# phono_preamp.net
KiCad netlist of a schematic drawn in EAGLE
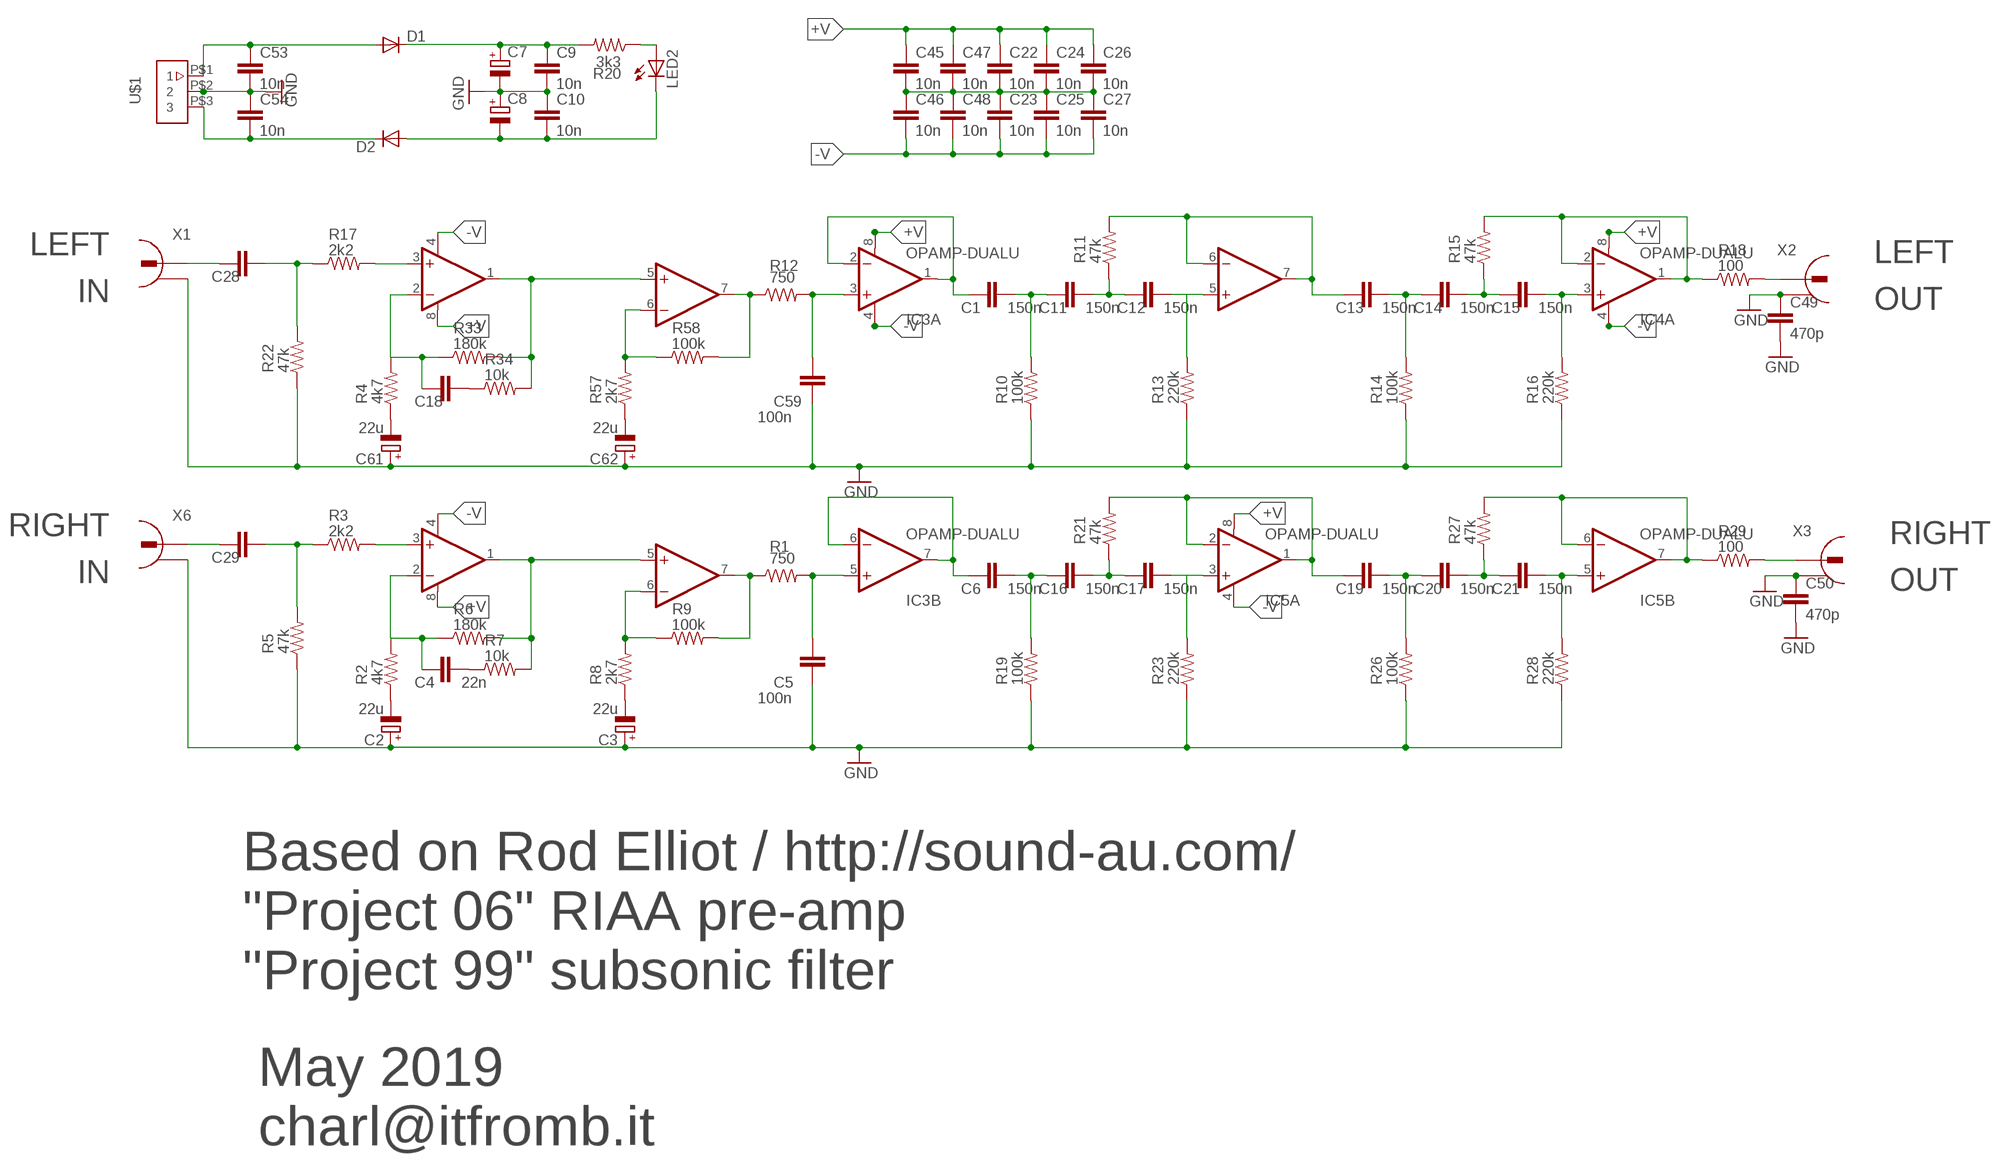
[diagram p0: schematic, sheet 1]

(export (version "E")
  (design (tool "Eeschema 10.0.6"))
  (components
    (comp (ref "C1")
      (value "150n")
      (footprint "eagle-import:C1206")
      (libsource (lib "eagle-import") (part "C-EUC1206"))
    )
    (comp (ref "C2")
      (value "22u")
      (footprint "eagle-import:PANASONIC_C")
      (libsource (lib "eagle-import") (part "CPOL-EUC"))
    )
    (comp (ref "C3")
      (value "22u")
      (footprint "eagle-import:PANASONIC_C")
      (libsource (lib "eagle-import") (part "CPOL-EUC"))
    )
    (comp (ref "C4")
      (value "22n")
      (footprint "eagle-import:C1206")
      (libsource (lib "eagle-import") (part "C-EUC1206"))
    )
    (comp (ref "C5")
      (value "100n")
      (footprint "eagle-import:C1206")
      (libsource (lib "eagle-import") (part "C-EUC1206"))
    )
    (comp (ref "C6")
      (value "150n")
      (footprint "eagle-import:C1206")
      (libsource (lib "eagle-import") (part "C-EUC1206"))
    )
    (comp (ref "C7")
      (value "CPOL-EUSANYO_SMD_F12")
      (footprint "eagle-import:SANYO-OSCON_SMD_F12")
      (libsource (lib "eagle-import") (part "stereo_5.1_mixer_CPOL-EUSANYO_SMD_F12"))
    )
    (comp (ref "C8")
      (value "CPOL-EUSANYO_SMD_F12")
      (footprint "eagle-import:SANYO-OSCON_SMD_F12")
      (libsource (lib "eagle-import") (part "stereo_5.1_mixer_CPOL-EUSANYO_SMD_F12"))
    )
    (comp (ref "C9")
      (value "10n")
      (footprint "eagle-import:C1206")
      (libsource (lib "eagle-import") (part "C-EUC1206"))
    )
    (comp (ref "C10")
      (value "10n")
      (footprint "eagle-import:C1206")
      (libsource (lib "eagle-import") (part "C-EUC1206"))
    )
    (comp (ref "C11")
      (value "150n")
      (footprint "eagle-import:C1206")
      (libsource (lib "eagle-import") (part "C-EUC1206"))
    )
    (comp (ref "C12")
      (value "150n")
      (footprint "eagle-import:C1206")
      (libsource (lib "eagle-import") (part "C-EUC1206"))
    )
    (comp (ref "C13")
      (value "150n")
      (footprint "eagle-import:C1206")
      (libsource (lib "eagle-import") (part "C-EUC1206"))
    )
    (comp (ref "C14")
      (value "150n")
      (footprint "eagle-import:C1206")
      (libsource (lib "eagle-import") (part "C-EUC1206"))
    )
    (comp (ref "C15")
      (value "150n")
      (footprint "eagle-import:C1206")
      (libsource (lib "eagle-import") (part "C-EUC1206"))
    )
    (comp (ref "C16")
      (value "150n")
      (footprint "eagle-import:C1206")
      (libsource (lib "eagle-import") (part "C-EUC1206"))
    )
    (comp (ref "C17")
      (value "150n")
      (footprint "eagle-import:C1206")
      (libsource (lib "eagle-import") (part "C-EUC1206"))
    )
    (comp (ref "C18")
      (value "22n")
      (footprint "eagle-import:C1206")
      (libsource (lib "eagle-import") (part "C-EUC1206"))
    )
    (comp (ref "C19")
      (value "150n")
      (footprint "eagle-import:C1206")
      (libsource (lib "eagle-import") (part "C-EUC1206"))
    )
    (comp (ref "C20")
      (value "150n")
      (footprint "eagle-import:C1206")
      (libsource (lib "eagle-import") (part "C-EUC1206"))
    )
    (comp (ref "C21")
      (value "150n")
      (footprint "eagle-import:C1206")
      (libsource (lib "eagle-import") (part "C-EUC1206"))
    )
    (comp (ref "C22")
      (value "10n")
      (footprint "eagle-import:C1206")
      (libsource (lib "eagle-import") (part "C-EUC1206"))
    )
    (comp (ref "C23")
      (value "10n")
      (footprint "eagle-import:C1206")
      (libsource (lib "eagle-import") (part "C-EUC1206"))
    )
    (comp (ref "C24")
      (value "10n")
      (footprint "eagle-import:C1206")
      (libsource (lib "eagle-import") (part "C-EUC1206"))
    )
    (comp (ref "C25")
      (value "10n")
      (footprint "eagle-import:C1206")
      (libsource (lib "eagle-import") (part "C-EUC1206"))
    )
    (comp (ref "C26")
      (value "10n")
      (footprint "eagle-import:C1206")
      (libsource (lib "eagle-import") (part "C-EUC1206"))
    )
    (comp (ref "C27")
      (value "10n")
      (footprint "eagle-import:C1206")
      (libsource (lib "eagle-import") (part "C-EUC1206"))
    )
    (comp (ref "C28")
      (value "C-EUC1206")
      (footprint "eagle-import:C1206")
      (libsource (lib "eagle-import") (part "C-EUC1206"))
    )
    (comp (ref "C29")
      (value "C-EUC1206")
      (footprint "eagle-import:C1206")
      (libsource (lib "eagle-import") (part "C-EUC1206"))
    )
    (comp (ref "C45")
      (value "10n")
      (footprint "eagle-import:C1206")
      (libsource (lib "eagle-import") (part "C-EUC1206"))
    )
    (comp (ref "C46")
      (value "10n")
      (footprint "eagle-import:C1206")
      (libsource (lib "eagle-import") (part "C-EUC1206"))
    )
    (comp (ref "C47")
      (value "10n")
      (footprint "eagle-import:C1206")
      (libsource (lib "eagle-import") (part "C-EUC1206"))
    )
    (comp (ref "C48")
      (value "10n")
      (footprint "eagle-import:C1206")
      (libsource (lib "eagle-import") (part "C-EUC1206"))
    )
    (comp (ref "C49")
      (value "470p")
      (footprint "eagle-import:C1206")
      (libsource (lib "eagle-import") (part "C-EUC1206"))
    )
    (comp (ref "C50")
      (value "470p")
      (footprint "eagle-import:C1206")
      (libsource (lib "eagle-import") (part "C-EUC1206"))
    )
    (comp (ref "C53")
      (value "10n")
      (footprint "eagle-import:C1206")
      (libsource (lib "eagle-import") (part "C-EUC1206"))
    )
    (comp (ref "C54")
      (value "10n")
      (footprint "eagle-import:C1206")
      (libsource (lib "eagle-import") (part "C-EUC1206"))
    )
    (comp (ref "C59")
      (value "100n")
      (footprint "eagle-import:C1206")
      (libsource (lib "eagle-import") (part "C-EUC1206"))
    )
    (comp (ref "C61")
      (value "22u")
      (footprint "eagle-import:PANASONIC_C")
      (libsource (lib "eagle-import") (part "CPOL-EUC"))
    )
    (comp (ref "C62")
      (value "22u")
      (footprint "eagle-import:PANASONIC_C")
      (libsource (lib "eagle-import") (part "CPOL-EUC"))
    )
    (comp (ref "D1")
      (value "DIODE-DO214AA")
      (footprint "eagle-import:DO214AA")
      (libsource (lib "eagle-import") (part "DIODE-DO214AA"))
    )
    (comp (ref "D2")
      (value "DIODE-DO214AA")
      (footprint "eagle-import:DO214AA")
      (libsource (lib "eagle-import") (part "DIODE-DO214AA"))
    )
    (comp (ref "IC1")
      (value "OPAMP-DUALU")
      (footprint "eagle-import:SO08")
      (libsource (lib "eagle-import") (part "OPAMP-DUALU"))
    )
    (comp (ref "IC2")
      (value "OPAMP-DUALU")
      (footprint "eagle-import:SO08")
      (libsource (lib "eagle-import") (part "OPAMP-DUALU"))
    )
    (comp (ref "IC3")
      (value "OPAMP-DUALU")
      (footprint "eagle-import:SO08")
      (libsource (lib "eagle-import") (part "OPAMP-DUALU"))
    )
    (comp (ref "IC4")
      (value "OPAMP-DUALU")
      (footprint "eagle-import:SO08")
      (libsource (lib "eagle-import") (part "OPAMP-DUALU"))
    )
    (comp (ref "IC5")
      (value "OPAMP-DUALU")
      (footprint "eagle-import:SO08")
      (libsource (lib "eagle-import") (part "OPAMP-DUALU"))
    )
    (comp (ref "LED2")
      (value "LEDCHIPLED_1206")
      (footprint "eagle-import:CHIPLED_1206")
      (libsource (lib "eagle-import") (part "LEDCHIPLED_1206"))
    )
    (comp (ref "R1")
      (value "750")
      (footprint "eagle-import:M1206")
      (libsource (lib "eagle-import") (part "R-US_M1206"))
    )
    (comp (ref "R2")
      (value "4k7")
      (footprint "eagle-import:M1206")
      (libsource (lib "eagle-import") (part "R-US_M1206"))
    )
    (comp (ref "R3")
      (value "2k2")
      (footprint "eagle-import:M1206")
      (libsource (lib "eagle-import") (part "R-US_M1206"))
    )
    (comp (ref "R4")
      (value "4k7")
      (footprint "eagle-import:M1206")
      (libsource (lib "eagle-import") (part "R-US_M1206"))
    )
    (comp (ref "R5")
      (value "47k")
      (footprint "eagle-import:M1206")
      (libsource (lib "eagle-import") (part "R-US_M1206"))
    )
    (comp (ref "R6")
      (value "180k")
      (footprint "eagle-import:M1206")
      (libsource (lib "eagle-import") (part "R-US_M1206"))
    )
    (comp (ref "R7")
      (value "10k")
      (footprint "eagle-import:M1206")
      (libsource (lib "eagle-import") (part "R-US_M1206"))
    )
    (comp (ref "R8")
      (value "2k7")
      (footprint "eagle-import:M1206")
      (libsource (lib "eagle-import") (part "R-US_M1206"))
    )
    (comp (ref "R9")
      (value "100k")
      (footprint "eagle-import:M1206")
      (libsource (lib "eagle-import") (part "R-US_M1206"))
    )
    (comp (ref "R10")
      (value "100k")
      (footprint "eagle-import:M1206")
      (libsource (lib "eagle-import") (part "R-US_M1206"))
    )
    (comp (ref "R11")
      (value "47k")
      (footprint "eagle-import:M1206")
      (libsource (lib "eagle-import") (part "R-US_M1206"))
    )
    (comp (ref "R12")
      (value "750")
      (footprint "eagle-import:M1206")
      (libsource (lib "eagle-import") (part "R-US_M1206"))
    )
    (comp (ref "R13")
      (value "220k")
      (footprint "eagle-import:M1206")
      (libsource (lib "eagle-import") (part "R-US_M1206"))
    )
    (comp (ref "R14")
      (value "100k")
      (footprint "eagle-import:M1206")
      (libsource (lib "eagle-import") (part "R-US_M1206"))
    )
    (comp (ref "R15")
      (value "47k")
      (footprint "eagle-import:M1206")
      (libsource (lib "eagle-import") (part "R-US_M1206"))
    )
    (comp (ref "R16")
      (value "220k")
      (footprint "eagle-import:M1206")
      (libsource (lib "eagle-import") (part "R-US_M1206"))
    )
    (comp (ref "R17")
      (value "2k2")
      (footprint "eagle-import:M1206")
      (libsource (lib "eagle-import") (part "R-US_M1206"))
    )
    (comp (ref "R18")
      (value "100")
      (footprint "eagle-import:M1206")
      (libsource (lib "eagle-import") (part "R-US_M1206"))
    )
    (comp (ref "R19")
      (value "100k")
      (footprint "eagle-import:M1206")
      (libsource (lib "eagle-import") (part "R-US_M1206"))
    )
    (comp (ref "R20")
      (value "3k3")
      (footprint "eagle-import:M1206")
      (libsource (lib "eagle-import") (part "R-US_M1206"))
    )
    (comp (ref "R21")
      (value "47k")
      (footprint "eagle-import:M1206")
      (libsource (lib "eagle-import") (part "R-US_M1206"))
    )
    (comp (ref "R22")
      (value "47k")
      (footprint "eagle-import:M1206")
      (libsource (lib "eagle-import") (part "R-US_M1206"))
    )
    (comp (ref "R23")
      (value "220k")
      (footprint "eagle-import:M1206")
      (libsource (lib "eagle-import") (part "R-US_M1206"))
    )
    (comp (ref "R26")
      (value "100k")
      (footprint "eagle-import:M1206")
      (libsource (lib "eagle-import") (part "R-US_M1206"))
    )
    (comp (ref "R27")
      (value "47k")
      (footprint "eagle-import:M1206")
      (libsource (lib "eagle-import") (part "R-US_M1206"))
    )
    (comp (ref "R28")
      (value "220k")
      (footprint "eagle-import:M1206")
      (libsource (lib "eagle-import") (part "R-US_M1206"))
    )
    (comp (ref "R29")
      (value "100")
      (footprint "eagle-import:M1206")
      (libsource (lib "eagle-import") (part "R-US_M1206"))
    )
    (comp (ref "R33")
      (value "180k")
      (footprint "eagle-import:M1206")
      (libsource (lib "eagle-import") (part "R-US_M1206"))
    )
    (comp (ref "R34")
      (value "10k")
      (footprint "eagle-import:M1206")
      (libsource (lib "eagle-import") (part "R-US_M1206"))
    )
    (comp (ref "R57")
      (value "2k7")
      (footprint "eagle-import:M1206")
      (libsource (lib "eagle-import") (part "R-US_M1206"))
    )
    (comp (ref "R58")
      (value "100k")
      (footprint "eagle-import:M1206")
      (libsource (lib "eagle-import") (part "R-US_M1206"))
    )
    (comp (ref "U$1")
      (value "3-PIN-JST-CONN-1.25MM-PITCH")
      (footprint "eagle-import:S3B-PH-VERTICAL")
      (libsource (lib "eagle-import") (part "3-PIN-JST-CONN-1.25MM-PITCH"))
    )
    (comp (ref "X1")
      (value "736880-49RCA-REAR-MOUNT")
      (footprint "eagle-import:RCA-REAR-MOUNT")
      (libsource (lib "eagle-import") (part "736880-49RCA-REAR-MOUNT"))
    )
    (comp (ref "X2")
      (value "736880-49RCA-REAR-MOUNT")
      (footprint "eagle-import:RCA-REAR-MOUNT")
      (libsource (lib "eagle-import") (part "736880-49RCA-REAR-MOUNT"))
    )
    (comp (ref "X3")
      (value "736880-49RCA-REAR-MOUNT")
      (footprint "eagle-import:RCA-REAR-MOUNT")
      (libsource (lib "eagle-import") (part "736880-49RCA-REAR-MOUNT"))
    )
    (comp (ref "X6")
      (value "736880-49RCA-REAR-MOUNT")
      (footprint "eagle-import:RCA-REAR-MOUNT")
      (libsource (lib "eagle-import") (part "736880-49RCA-REAR-MOUNT"))
    )
  )
  (nets
    (net (code "1") (name "+V") (class "Default")
      (node (ref "C22") (pin "1") (pinfunction "1_1") (pintype "passive"))
      (node (ref "C24") (pin "1") (pinfunction "1_1") (pintype "passive"))
      (node (ref "C26") (pin "1") (pinfunction "1_1") (pintype "passive"))
      (node (ref "C45") (pin "1") (pinfunction "1_1") (pintype "passive"))
      (node (ref "C47") (pin "1") (pinfunction "1_1") (pintype "passive"))
      (node (ref "C7") (pin "+") (pinfunction "+_+") (pintype "passive"))
      (node (ref "C9") (pin "1") (pinfunction "1_1") (pintype "passive"))
      (node (ref "D1") (pin "C") (pinfunction "C_C") (pintype "passive"))
      (node (ref "IC1") (pin "8") (pinfunction "V+_8") (pintype "power_in"))
      (node (ref "IC2") (pin "8") (pinfunction "V+_8") (pintype "power_in"))
      (node (ref "IC3") (pin "8") (pinfunction "V+_8") (pintype "power_in"))
      (node (ref "IC4") (pin "8") (pinfunction "V+_8") (pintype "power_in"))
      (node (ref "IC5") (pin "8") (pinfunction "V+_8") (pintype "power_in"))
      (node (ref "R20") (pin "2") (pinfunction "2_2") (pintype "passive"))
    )
    (net (code "2") (name "-V") (class "Default")
      (node (ref "C10") (pin "2") (pinfunction "2_2") (pintype "passive"))
      (node (ref "C23") (pin "2") (pinfunction "2_2") (pintype "passive"))
      (node (ref "C25") (pin "2") (pinfunction "2_2") (pintype "passive"))
      (node (ref "C27") (pin "2") (pinfunction "2_2") (pintype "passive"))
      (node (ref "C46") (pin "2") (pinfunction "2_2") (pintype "passive"))
      (node (ref "C48") (pin "2") (pinfunction "2_2") (pintype "passive"))
      (node (ref "C8") (pin "-") (pinfunction "-_-") (pintype "passive"))
      (node (ref "D2") (pin "A") (pinfunction "A_A") (pintype "passive"))
      (node (ref "IC1") (pin "4") (pinfunction "V-_4") (pintype "power_in"))
      (node (ref "IC2") (pin "4") (pinfunction "V-_4") (pintype "power_in"))
      (node (ref "IC3") (pin "4") (pinfunction "V-_4") (pintype "power_in"))
      (node (ref "IC4") (pin "4") (pinfunction "V-_4") (pintype "power_in"))
      (node (ref "IC5") (pin "4") (pinfunction "V-_4") (pintype "power_in"))
      (node (ref "LED2") (pin "C") (pinfunction "C_C") (pintype "passive"))
    )
    (net (code "3") (name "GND") (class "Default")
      (node (ref "C10") (pin "1") (pinfunction "1_1") (pintype "passive"))
      (node (ref "C2") (pin "+") (pinfunction "+_+") (pintype "passive"))
      (node (ref "C22") (pin "2") (pinfunction "2_2") (pintype "passive"))
      (node (ref "C23") (pin "1") (pinfunction "1_1") (pintype "passive"))
      (node (ref "C24") (pin "2") (pinfunction "2_2") (pintype "passive"))
      (node (ref "C25") (pin "1") (pinfunction "1_1") (pintype "passive"))
      (node (ref "C26") (pin "2") (pinfunction "2_2") (pintype "passive"))
      (node (ref "C27") (pin "1") (pinfunction "1_1") (pintype "passive"))
      (node (ref "C3") (pin "+") (pinfunction "+_+") (pintype "passive"))
      (node (ref "C45") (pin "2") (pinfunction "2_2") (pintype "passive"))
      (node (ref "C46") (pin "1") (pinfunction "1_1") (pintype "passive"))
      (node (ref "C47") (pin "2") (pinfunction "2_2") (pintype "passive"))
      (node (ref "C48") (pin "1") (pinfunction "1_1") (pintype "passive"))
      (node (ref "C49") (pin "1") (pinfunction "1_1") (pintype "passive"))
      (node (ref "C49") (pin "2") (pinfunction "2_2") (pintype "passive"))
      (node (ref "C5") (pin "1") (pinfunction "1_1") (pintype "passive"))
      (node (ref "C50") (pin "1") (pinfunction "1_1") (pintype "passive"))
      (node (ref "C50") (pin "2") (pinfunction "2_2") (pintype "passive"))
      (node (ref "C53") (pin "2") (pinfunction "2_2") (pintype "passive"))
      (node (ref "C54") (pin "1") (pinfunction "1_1") (pintype "passive"))
      (node (ref "C59") (pin "1") (pinfunction "1_1") (pintype "passive"))
      (node (ref "C61") (pin "+") (pinfunction "+_+") (pintype "passive"))
      (node (ref "C62") (pin "+") (pinfunction "+_+") (pintype "passive"))
      (node (ref "C7") (pin "-") (pinfunction "-_-") (pintype "passive"))
      (node (ref "C8") (pin "+") (pinfunction "+_+") (pintype "passive"))
      (node (ref "C9") (pin "2") (pinfunction "2_2") (pintype "passive"))
      (node (ref "R10") (pin "1") (pinfunction "1_1") (pintype "passive"))
      (node (ref "R13") (pin "1") (pinfunction "1_1") (pintype "passive"))
      (node (ref "R14") (pin "1") (pinfunction "1_1") (pintype "passive"))
      (node (ref "R16") (pin "1") (pinfunction "1_1") (pintype "passive"))
      (node (ref "R19") (pin "1") (pinfunction "1_1") (pintype "passive"))
      (node (ref "R22") (pin "1") (pinfunction "1_1") (pintype "passive"))
      (node (ref "R23") (pin "1") (pinfunction "1_1") (pintype "passive"))
      (node (ref "R26") (pin "1") (pinfunction "1_1") (pintype "passive"))
      (node (ref "R28") (pin "1") (pinfunction "1_1") (pintype "passive"))
      (node (ref "R5") (pin "1") (pinfunction "1_1") (pintype "passive"))
      (node (ref "U$1") (pin "P$2") (pinfunction "2_P$2") (pintype "passive"))
      (node (ref "X1") (pin "RING") (pinfunction "2_RING") (pintype "passive"))
      (node (ref "X2") (pin "RING") (pinfunction "2_RING") (pintype "passive"))
      (node (ref "X3") (pin "RING") (pinfunction "2_RING") (pintype "passive"))
      (node (ref "X6") (pin "RING") (pinfunction "2_RING") (pintype "passive"))
    )
    (net (code "4") (name "Net-(C1-Pad2)") (class "Default")
      (node (ref "C1") (pin "2") (pinfunction "2_2") (pintype "passive"))
      (node (ref "C11") (pin "1") (pinfunction "1_1") (pintype "passive"))
      (node (ref "R10") (pin "2") (pinfunction "2_2") (pintype "passive"))
    )
    (net (code "5") (name "Net-(C2-Pad-)") (class "Default")
      (node (ref "C2") (pin "-") (pinfunction "-_-") (pintype "passive"))
      (node (ref "R2") (pin "1") (pinfunction "1_1") (pintype "passive"))
    )
    (net (code "6") (name "Net-(C3-Pad-)") (class "Default")
      (node (ref "C3") (pin "-") (pinfunction "-_-") (pintype "passive"))
      (node (ref "R8") (pin "1") (pinfunction "1_1") (pintype "passive"))
    )
    (net (code "7") (name "Net-(C4-Pad2)") (class "Default")
      (node (ref "C4") (pin "2") (pinfunction "2_2") (pintype "passive"))
      (node (ref "R7") (pin "1") (pinfunction "1_1") (pintype "passive"))
    )
    (net (code "8") (name "Net-(C11-Pad2)") (class "Default")
      (node (ref "C11") (pin "2") (pinfunction "2_2") (pintype "passive"))
      (node (ref "C12") (pin "1") (pinfunction "1_1") (pintype "passive"))
      (node (ref "R11") (pin "1") (pinfunction "1_1") (pintype "passive"))
    )
    (net (code "9") (name "Net-(C13-Pad2)") (class "Default")
      (node (ref "C13") (pin "2") (pinfunction "2_2") (pintype "passive"))
      (node (ref "C14") (pin "1") (pinfunction "1_1") (pintype "passive"))
      (node (ref "R14") (pin "2") (pinfunction "2_2") (pintype "passive"))
    )
    (net (code "10") (name "Net-(C14-Pad2)") (class "Default")
      (node (ref "C14") (pin "2") (pinfunction "2_2") (pintype "passive"))
      (node (ref "C15") (pin "1") (pinfunction "1_1") (pintype "passive"))
      (node (ref "R15") (pin "1") (pinfunction "1_1") (pintype "passive"))
    )
    (net (code "11") (name "Net-(C16-Pad1)") (class "Default")
      (node (ref "C16") (pin "1") (pinfunction "1_1") (pintype "passive"))
      (node (ref "C6") (pin "2") (pinfunction "2_2") (pintype "passive"))
      (node (ref "R19") (pin "2") (pinfunction "2_2") (pintype "passive"))
    )
    (net (code "12") (name "Net-(C16-Pad2)") (class "Default")
      (node (ref "C16") (pin "2") (pinfunction "2_2") (pintype "passive"))
      (node (ref "C17") (pin "1") (pinfunction "1_1") (pintype "passive"))
      (node (ref "R21") (pin "1") (pinfunction "1_1") (pintype "passive"))
    )
    (net (code "13") (name "Net-(C18-Pad2)") (class "Default")
      (node (ref "C18") (pin "2") (pinfunction "2_2") (pintype "passive"))
      (node (ref "R34") (pin "1") (pinfunction "1_1") (pintype "passive"))
    )
    (net (code "14") (name "Net-(C19-Pad2)") (class "Default")
      (node (ref "C19") (pin "2") (pinfunction "2_2") (pintype "passive"))
      (node (ref "C20") (pin "1") (pinfunction "1_1") (pintype "passive"))
      (node (ref "R26") (pin "2") (pinfunction "2_2") (pintype "passive"))
    )
    (net (code "15") (name "Net-(C20-Pad2)") (class "Default")
      (node (ref "C20") (pin "2") (pinfunction "2_2") (pintype "passive"))
      (node (ref "C21") (pin "1") (pinfunction "1_1") (pintype "passive"))
      (node (ref "R27") (pin "1") (pinfunction "1_1") (pintype "passive"))
    )
    (net (code "16") (name "Net-(C28-Pad2)") (class "Default")
      (node (ref "C28") (pin "2") (pinfunction "2_2") (pintype "passive"))
      (node (ref "R17") (pin "1") (pinfunction "1_1") (pintype "passive"))
      (node (ref "R22") (pin "2") (pinfunction "2_2") (pintype "passive"))
    )
    (net (code "17") (name "Net-(C29-Pad2)") (class "Default")
      (node (ref "C29") (pin "2") (pinfunction "2_2") (pintype "passive"))
      (node (ref "R3") (pin "1") (pinfunction "1_1") (pintype "passive"))
      (node (ref "R5") (pin "2") (pinfunction "2_2") (pintype "passive"))
    )
    (net (code "18") (name "Net-(C61-Pad-)") (class "Default")
      (node (ref "C61") (pin "-") (pinfunction "-_-") (pintype "passive"))
      (node (ref "R4") (pin "1") (pinfunction "1_1") (pintype "passive"))
    )
    (net (code "19") (name "Net-(C62-Pad-)") (class "Default")
      (node (ref "C62") (pin "-") (pinfunction "-_-") (pintype "passive"))
      (node (ref "R57") (pin "1") (pinfunction "1_1") (pintype "passive"))
    )
    (net (code "20") (name "Net-(IC1A-+IN)") (class "Default")
      (node (ref "IC1") (pin "3") (pinfunction "+IN_3") (pintype "input"))
      (node (ref "R3") (pin "2") (pinfunction "2_2") (pintype "passive"))
    )
    (net (code "21") (name "Net-(IC1A--IN)") (class "Default")
      (node (ref "C4") (pin "1") (pinfunction "1_1") (pintype "passive"))
      (node (ref "IC1") (pin "2") (pinfunction "-IN_2") (pintype "input"))
      (node (ref "R2") (pin "2") (pinfunction "2_2") (pintype "passive"))
      (node (ref "R6") (pin "1") (pinfunction "1_1") (pintype "passive"))
    )
    (net (code "22") (name "Net-(IC1A-OUT)") (class "Default")
      (node (ref "IC1") (pin "1") (pinfunction "OUT_1") (pintype "output"))
      (node (ref "IC1") (pin "5") (pinfunction "+IN_5") (pintype "input"))
      (node (ref "R6") (pin "2") (pinfunction "2_2") (pintype "passive"))
      (node (ref "R7") (pin "2") (pinfunction "2_2") (pintype "passive"))
    )
    (net (code "23") (name "Net-(IC1B--IN)") (class "Default")
      (node (ref "IC1") (pin "6") (pinfunction "-IN_6") (pintype "input"))
      (node (ref "R8") (pin "2") (pinfunction "2_2") (pintype "passive"))
      (node (ref "R9") (pin "1") (pinfunction "1_1") (pintype "passive"))
    )
    (net (code "24") (name "Net-(IC1B-OUT)") (class "Default")
      (node (ref "IC1") (pin "7") (pinfunction "OUT_7") (pintype "output"))
      (node (ref "R1") (pin "1") (pinfunction "1_1") (pintype "passive"))
      (node (ref "R9") (pin "2") (pinfunction "2_2") (pintype "passive"))
    )
    (net (code "25") (name "Net-(IC2A-+IN)") (class "Default")
      (node (ref "IC2") (pin "3") (pinfunction "+IN_3") (pintype "input"))
      (node (ref "R17") (pin "2") (pinfunction "2_2") (pintype "passive"))
    )
    (net (code "26") (name "Net-(IC2A--IN)") (class "Default")
      (node (ref "C18") (pin "1") (pinfunction "1_1") (pintype "passive"))
      (node (ref "IC2") (pin "2") (pinfunction "-IN_2") (pintype "input"))
      (node (ref "R33") (pin "1") (pinfunction "1_1") (pintype "passive"))
      (node (ref "R4") (pin "2") (pinfunction "2_2") (pintype "passive"))
    )
    (net (code "27") (name "Net-(IC2A-OUT)") (class "Default")
      (node (ref "IC2") (pin "1") (pinfunction "OUT_1") (pintype "output"))
      (node (ref "IC2") (pin "5") (pinfunction "+IN_5") (pintype "input"))
      (node (ref "R33") (pin "2") (pinfunction "2_2") (pintype "passive"))
      (node (ref "R34") (pin "2") (pinfunction "2_2") (pintype "passive"))
    )
    (net (code "28") (name "Net-(IC2B--IN)") (class "Default")
      (node (ref "IC2") (pin "6") (pinfunction "-IN_6") (pintype "input"))
      (node (ref "R57") (pin "2") (pinfunction "2_2") (pintype "passive"))
      (node (ref "R58") (pin "1") (pinfunction "1_1") (pintype "passive"))
    )
    (net (code "29") (name "Net-(IC2B-OUT)") (class "Default")
      (node (ref "IC2") (pin "7") (pinfunction "OUT_7") (pintype "output"))
      (node (ref "R12") (pin "1") (pinfunction "1_1") (pintype "passive"))
      (node (ref "R58") (pin "2") (pinfunction "2_2") (pintype "passive"))
    )
    (net (code "30") (name "Net-(IC3A-+IN)") (class "Default")
      (node (ref "C59") (pin "2") (pinfunction "2_2") (pintype "passive"))
      (node (ref "IC3") (pin "3") (pinfunction "+IN_3") (pintype "input"))
      (node (ref "R12") (pin "2") (pinfunction "2_2") (pintype "passive"))
    )
    (net (code "31") (name "Net-(IC3A--IN)") (class "Default")
      (node (ref "C1") (pin "1") (pinfunction "1_1") (pintype "passive"))
      (node (ref "IC3") (pin "1") (pinfunction "OUT_1") (pintype "output"))
      (node (ref "IC3") (pin "2") (pinfunction "-IN_2") (pintype "input"))
    )
    (net (code "32") (name "Net-(IC3B-+IN)") (class "Default")
      (node (ref "C5") (pin "2") (pinfunction "2_2") (pintype "passive"))
      (node (ref "IC3") (pin "5") (pinfunction "+IN_5") (pintype "input"))
      (node (ref "R1") (pin "2") (pinfunction "2_2") (pintype "passive"))
    )
    (net (code "33") (name "Net-(IC3B--IN)") (class "Default")
      (node (ref "C6") (pin "1") (pinfunction "1_1") (pintype "passive"))
      (node (ref "IC3") (pin "6") (pinfunction "-IN_6") (pintype "input"))
      (node (ref "IC3") (pin "7") (pinfunction "OUT_7") (pintype "output"))
    )
    (net (code "34") (name "Net-(IC4A-+IN)") (class "Default")
      (node (ref "C15") (pin "2") (pinfunction "2_2") (pintype "passive"))
      (node (ref "IC4") (pin "3") (pinfunction "+IN_3") (pintype "input"))
      (node (ref "R16") (pin "2") (pinfunction "2_2") (pintype "passive"))
    )
    (net (code "35") (name "Net-(IC4A--IN)") (class "Default")
      (node (ref "IC4") (pin "1") (pinfunction "OUT_1") (pintype "output"))
      (node (ref "IC4") (pin "2") (pinfunction "-IN_2") (pintype "input"))
      (node (ref "R15") (pin "2") (pinfunction "2_2") (pintype "passive"))
      (node (ref "R18") (pin "1") (pinfunction "1_1") (pintype "passive"))
    )
    (net (code "36") (name "Net-(IC4B-+IN)") (class "Default")
      (node (ref "C12") (pin "2") (pinfunction "2_2") (pintype "passive"))
      (node (ref "IC4") (pin "5") (pinfunction "+IN_5") (pintype "input"))
      (node (ref "R13") (pin "2") (pinfunction "2_2") (pintype "passive"))
    )
    (net (code "37") (name "Net-(IC4B--IN)") (class "Default")
      (node (ref "C13") (pin "1") (pinfunction "1_1") (pintype "passive"))
      (node (ref "IC4") (pin "6") (pinfunction "-IN_6") (pintype "input"))
      (node (ref "IC4") (pin "7") (pinfunction "OUT_7") (pintype "output"))
      (node (ref "R11") (pin "2") (pinfunction "2_2") (pintype "passive"))
    )
    (net (code "38") (name "Net-(IC5A-+IN)") (class "Default")
      (node (ref "C17") (pin "2") (pinfunction "2_2") (pintype "passive"))
      (node (ref "IC5") (pin "3") (pinfunction "+IN_3") (pintype "input"))
      (node (ref "R23") (pin "2") (pinfunction "2_2") (pintype "passive"))
    )
    (net (code "39") (name "Net-(IC5A--IN)") (class "Default")
      (node (ref "C19") (pin "1") (pinfunction "1_1") (pintype "passive"))
      (node (ref "IC5") (pin "1") (pinfunction "OUT_1") (pintype "output"))
      (node (ref "IC5") (pin "2") (pinfunction "-IN_2") (pintype "input"))
      (node (ref "R21") (pin "2") (pinfunction "2_2") (pintype "passive"))
    )
    (net (code "40") (name "Net-(IC5B-+IN)") (class "Default")
      (node (ref "C21") (pin "2") (pinfunction "2_2") (pintype "passive"))
      (node (ref "IC5") (pin "5") (pinfunction "+IN_5") (pintype "input"))
      (node (ref "R28") (pin "2") (pinfunction "2_2") (pintype "passive"))
    )
    (net (code "41") (name "Net-(IC5B--IN)") (class "Default")
      (node (ref "IC5") (pin "6") (pinfunction "-IN_6") (pintype "input"))
      (node (ref "IC5") (pin "7") (pinfunction "OUT_7") (pintype "output"))
      (node (ref "R27") (pin "2") (pinfunction "2_2") (pintype "passive"))
      (node (ref "R29") (pin "1") (pinfunction "1_1") (pintype "passive"))
    )
    (net (code "42") (name "Net-(LED2-PadA)") (class "Default")
      (node (ref "LED2") (pin "A") (pinfunction "A_A") (pintype "passive"))
      (node (ref "R20") (pin "1") (pinfunction "1_1") (pintype "passive"))
    )
    (net (code "43") (name "Net-(U$1-1)") (class "Default")
      (node (ref "C53") (pin "1") (pinfunction "1_1") (pintype "passive"))
      (node (ref "D1") (pin "A") (pinfunction "A_A") (pintype "passive"))
      (node (ref "U$1") (pin "P$1") (pinfunction "1_P$1") (pintype "passive"))
    )
    (net (code "44") (name "Net-(U$1-3)") (class "Default")
      (node (ref "C54") (pin "2") (pinfunction "2_2") (pintype "passive"))
      (node (ref "D2") (pin "C") (pinfunction "C_C") (pintype "passive"))
      (node (ref "U$1") (pin "P$3") (pinfunction "3_P$3") (pintype "passive"))
    )
    (net (code "45") (name "Net-(X1-1)") (class "Default")
      (node (ref "C28") (pin "1") (pinfunction "1_1") (pintype "passive"))
      (node (ref "X1") (pin "SIGNAL") (pinfunction "1_SIGNAL") (pintype "passive"))
    )
    (net (code "46") (name "Net-(X2-1)") (class "Default")
      (node (ref "R18") (pin "2") (pinfunction "2_2") (pintype "passive"))
      (node (ref "X2") (pin "SIGNAL") (pinfunction "1_SIGNAL") (pintype "passive"))
    )
    (net (code "47") (name "Net-(X3-1)") (class "Default")
      (node (ref "R29") (pin "2") (pinfunction "2_2") (pintype "passive"))
      (node (ref "X3") (pin "SIGNAL") (pinfunction "1_SIGNAL") (pintype "passive"))
    )
    (net (code "48") (name "Net-(X6-1)") (class "Default")
      (node (ref "C29") (pin "1") (pinfunction "1_1") (pintype "passive"))
      (node (ref "X6") (pin "SIGNAL") (pinfunction "1_SIGNAL") (pintype "passive"))
    )
  )
)
